# hhv-dcdarknet.net
KiCad netlist of a schematic drawn in EAGLE
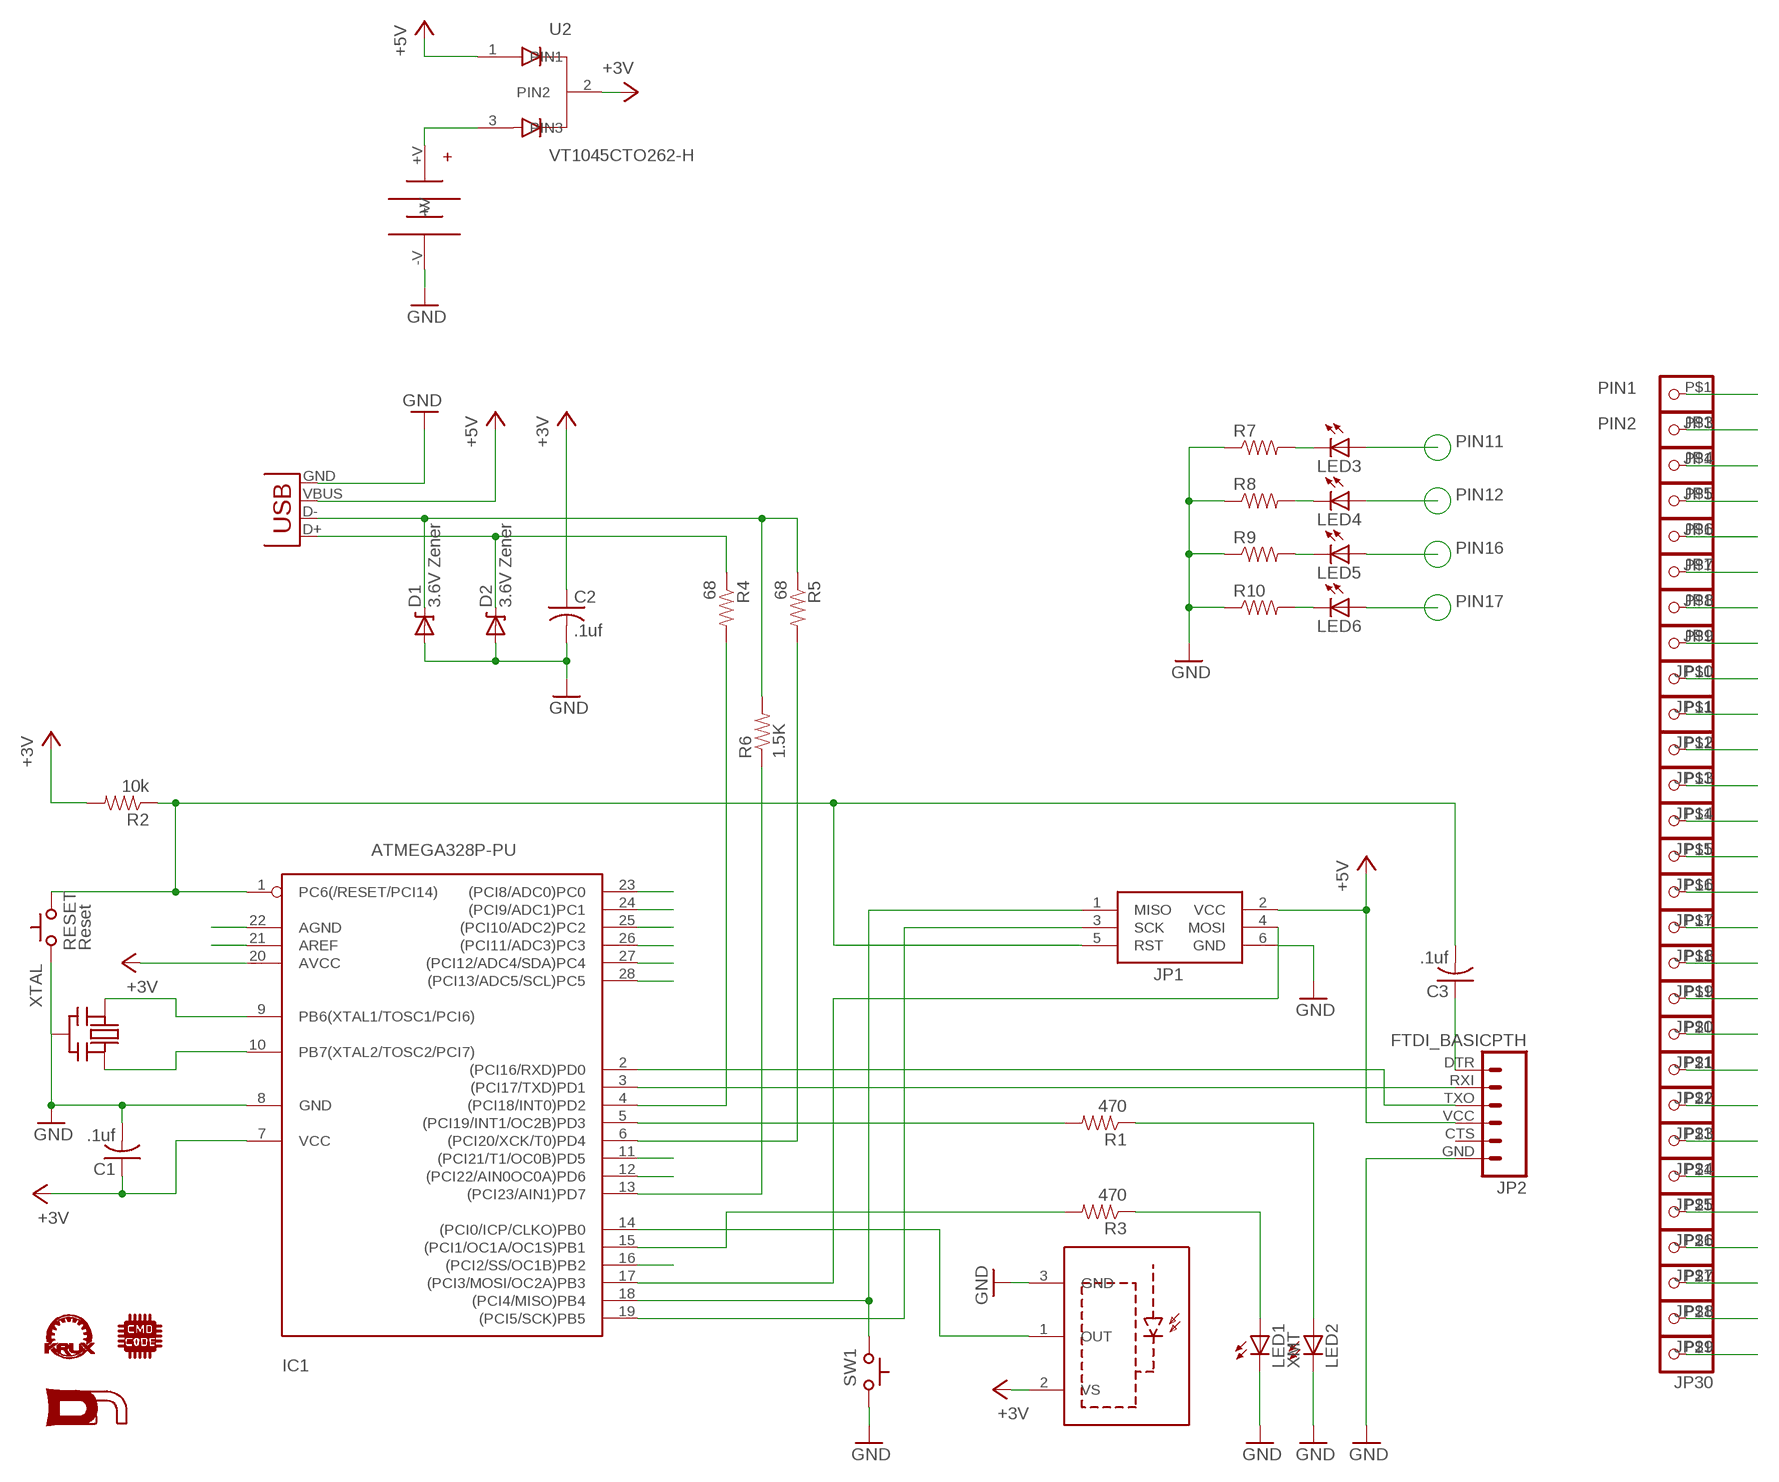
[diagram p0: schematic, sheet 1]

(export (version "E")
  (design (tool "Eeschema 10.0.6"))
  (components
    (comp (ref "C1")
      (value ".1uf")
      (footprint "eagle-import:C025-030X050")
      (libsource (lib "eagle-import") (part "C-US025-030X050"))
    )
    (comp (ref "C2")
      (value ".1uf")
      (footprint "eagle-import:C025-030X050")
      (libsource (lib "eagle-import") (part "C-US025-030X050"))
    )
    (comp (ref "C3")
      (value ".1uf")
      (footprint "eagle-import:C025-030X050")
      (libsource (lib "eagle-import") (part "C-US025-030X050"))
    )
    (comp (ref "D1")
      (value "3.6V Zener")
      (footprint "eagle-import:DIODE-ZENER")
      (libsource (lib "eagle-import") (part "DIODE-ZENERPTH"))
    )
    (comp (ref "D2")
      (value "3.6V Zener")
      (footprint "eagle-import:DIODE-ZENER")
      (libsource (lib "eagle-import") (part "DIODE-ZENERPTH"))
    )
    (comp (ref "IC1")
      (value "ATMEGA328P-PU")
      (footprint "eagle-import:DIL28-3")
      (libsource (lib "eagle-import") (part "ATMEGA168PV-10"))
    )
    (comp (ref "JP1")
      (value "JP1")
      (footprint "eagle-import:AVRISP")
      (libsource (lib "eagle-import") (part "AVRISP-6"))
    )
    (comp (ref "JP2")
      (value "FTDI_BASICPTH")
      (footprint "eagle-import:FTDI_BASIC")
      (libsource (lib "eagle-import") (part "FTDI_BASICPTH"))
    )
    (comp (ref "JP3")
      (value "PINHD-1X11X1_SQUARE")
      (footprint "eagle-import:1X1-SMALL_CUT")
      (libsource (lib "eagle-import") (part "PINHD-1X11X1_SQUARE"))
    )
    (comp (ref "JP4")
      (value "PINHD-1X11X1_SQUARE")
      (footprint "eagle-import:1X1-SMALL_CUT")
      (libsource (lib "eagle-import") (part "PINHD-1X11X1_SQUARE"))
    )
    (comp (ref "JP5")
      (value "PINHD-1X11X1_SQUARE")
      (footprint "eagle-import:1X1-SMALL_CUT")
      (libsource (lib "eagle-import") (part "PINHD-1X11X1_SQUARE"))
    )
    (comp (ref "JP6")
      (value "PINHD-1X11X1_SQUARE")
      (footprint "eagle-import:1X1-SMALL_CUT")
      (libsource (lib "eagle-import") (part "PINHD-1X11X1_SQUARE"))
    )
    (comp (ref "JP7")
      (value "PINHD-1X11X1_SQUARE")
      (footprint "eagle-import:1X1-SMALL_CUT")
      (libsource (lib "eagle-import") (part "PINHD-1X11X1_SQUARE"))
    )
    (comp (ref "JP8")
      (value "PINHD-1X11X1_SQUARE")
      (footprint "eagle-import:1X1-SMALL_CUT")
      (libsource (lib "eagle-import") (part "PINHD-1X11X1_SQUARE"))
    )
    (comp (ref "JP9")
      (value "PINHD-1X11X1_SQUARE")
      (footprint "eagle-import:1X1-SMALL_CUT")
      (libsource (lib "eagle-import") (part "PINHD-1X11X1_SQUARE"))
    )
    (comp (ref "JP10")
      (value "PINHD-1X11X1_SQUARE")
      (footprint "eagle-import:1X1-SMALL_CUT")
      (libsource (lib "eagle-import") (part "PINHD-1X11X1_SQUARE"))
    )
    (comp (ref "JP11")
      (value "PINHD-1X11X1_SQUARE")
      (footprint "eagle-import:1X1-SMALL_CUT")
      (libsource (lib "eagle-import") (part "PINHD-1X11X1_SQUARE"))
    )
    (comp (ref "JP12")
      (value "PINHD-1X11X1_SQUARE")
      (footprint "eagle-import:1X1-SMALL_CUT")
      (libsource (lib "eagle-import") (part "PINHD-1X11X1_SQUARE"))
    )
    (comp (ref "JP13")
      (value "PINHD-1X11X1_SQUARE")
      (footprint "eagle-import:1X1-SMALL_CUT")
      (libsource (lib "eagle-import") (part "PINHD-1X11X1_SQUARE"))
    )
    (comp (ref "JP14")
      (value "PINHD-1X11X1_SQUARE")
      (footprint "eagle-import:1X1-SMALL_CUT")
      (libsource (lib "eagle-import") (part "PINHD-1X11X1_SQUARE"))
    )
    (comp (ref "JP15")
      (value "PINHD-1X11X1_SQUARE")
      (footprint "eagle-import:1X1-SMALL_CUT")
      (libsource (lib "eagle-import") (part "PINHD-1X11X1_SQUARE"))
    )
    (comp (ref "JP16")
      (value "PINHD-1X11X1_SQUARE")
      (footprint "eagle-import:1X1-SMALL_CUT")
      (libsource (lib "eagle-import") (part "PINHD-1X11X1_SQUARE"))
    )
    (comp (ref "JP17")
      (value "PINHD-1X11X1_SQUARE")
      (footprint "eagle-import:1X1-SMALL_CUT")
      (libsource (lib "eagle-import") (part "PINHD-1X11X1_SQUARE"))
    )
    (comp (ref "JP18")
      (value "PINHD-1X11X1_SQUARE")
      (footprint "eagle-import:1X1-SMALL_CUT")
      (libsource (lib "eagle-import") (part "PINHD-1X11X1_SQUARE"))
    )
    (comp (ref "JP19")
      (value "PINHD-1X11X1_SQUARE")
      (footprint "eagle-import:1X1-SMALL_CUT")
      (libsource (lib "eagle-import") (part "PINHD-1X11X1_SQUARE"))
    )
    (comp (ref "JP20")
      (value "PINHD-1X11X1_SQUARE")
      (footprint "eagle-import:1X1-SMALL_CUT")
      (libsource (lib "eagle-import") (part "PINHD-1X11X1_SQUARE"))
    )
    (comp (ref "JP21")
      (value "PINHD-1X11X1_SQUARE")
      (footprint "eagle-import:1X1-SMALL_CUT")
      (libsource (lib "eagle-import") (part "PINHD-1X11X1_SQUARE"))
    )
    (comp (ref "JP22")
      (value "PINHD-1X11X1_SQUARE")
      (footprint "eagle-import:1X1-SMALL_CUT")
      (libsource (lib "eagle-import") (part "PINHD-1X11X1_SQUARE"))
    )
    (comp (ref "JP23")
      (value "PINHD-1X11X1_SQUARE")
      (footprint "eagle-import:1X1-SMALL_CUT")
      (libsource (lib "eagle-import") (part "PINHD-1X11X1_SQUARE"))
    )
    (comp (ref "JP24")
      (value "PINHD-1X11X1-SMALL")
      (footprint "eagle-import:1X1-SMALL")
      (libsource (lib "eagle-import") (part "PINHD-1X11X1-SMALL"))
    )
    (comp (ref "JP25")
      (value "PINHD-1X11X1-SMALL")
      (footprint "eagle-import:1X1-SMALL")
      (libsource (lib "eagle-import") (part "PINHD-1X11X1-SMALL"))
    )
    (comp (ref "JP26")
      (value "PINHD-1X11X1_SQUARE")
      (footprint "eagle-import:1X1-SMALL_CUT")
      (libsource (lib "eagle-import") (part "PINHD-1X11X1_SQUARE"))
    )
    (comp (ref "JP27")
      (value "PINHD-1X11X1-SMALL")
      (footprint "eagle-import:1X1-SMALL")
      (libsource (lib "eagle-import") (part "PINHD-1X11X1-SMALL"))
    )
    (comp (ref "JP28")
      (value "PINHD-1X11X1_SQUARE")
      (footprint "eagle-import:1X1-SMALL_CUT")
      (libsource (lib "eagle-import") (part "PINHD-1X11X1_SQUARE"))
    )
    (comp (ref "JP29")
      (value "PINHD-1X11X1-SMALL")
      (footprint "eagle-import:1X1-SMALL")
      (libsource (lib "eagle-import") (part "PINHD-1X11X1-SMALL"))
    )
    (comp (ref "JP30")
      (value "PINHD-1X11X1-SMALL")
      (footprint "eagle-import:1X1-SMALL")
      (libsource (lib "eagle-import") (part "PINHD-1X11X1-SMALL"))
    )
    (comp (ref "LED1")
      (value "XMT")
      (footprint "eagle-import:LED5MM-FLAT")
      (libsource (lib "eagle-import") (part "LED5MM-FLAT"))
    )
    (comp (ref "LED2")
      (value "LED5MM-FLAT")
      (footprint "eagle-import:LED5MM-FLAT")
      (libsource (lib "eagle-import") (part "LED5MM-FLAT"))
    )
    (comp (ref "LED3")
      (value "LED1206")
      (footprint "eagle-import:LED-1206")
      (libsource (lib "eagle-import") (part "SparkFun_LED1206"))
    )
    (comp (ref "LED4")
      (value "LED1206")
      (footprint "eagle-import:LED-1206")
      (libsource (lib "eagle-import") (part "SparkFun_LED1206"))
    )
    (comp (ref "LED5")
      (value "LED1206")
      (footprint "eagle-import:LED-1206")
      (libsource (lib "eagle-import") (part "SparkFun_LED1206"))
    )
    (comp (ref "LED6")
      (value "LED1206")
      (footprint "eagle-import:LED-1206")
      (libsource (lib "eagle-import") (part "SparkFun_LED1206"))
    )
    (comp (ref "R1")
      (value "470")
      (footprint "eagle-import:AXIAL-0.3")
      (libsource (lib "eagle-import") (part "RESISTORAXIAL-0.3"))
    )
    (comp (ref "R2")
      (value "10k")
      (footprint "eagle-import:AXIAL-0.3")
      (libsource (lib "eagle-import") (part "RESISTORAXIAL-0.3"))
    )
    (comp (ref "R3")
      (value "470")
      (footprint "eagle-import:AXIAL-0.3")
      (libsource (lib "eagle-import") (part "RESISTORAXIAL-0.3"))
    )
    (comp (ref "R4")
      (value "68")
      (footprint "eagle-import:AXIAL-0.3")
      (libsource (lib "eagle-import") (part "RESISTORAXIAL-0.3"))
    )
    (comp (ref "R5")
      (value "68")
      (footprint "eagle-import:AXIAL-0.3")
      (libsource (lib "eagle-import") (part "RESISTORAXIAL-0.3"))
    )
    (comp (ref "R6")
      (value "1.5K")
      (footprint "eagle-import:AXIAL-0.3")
      (libsource (lib "eagle-import") (part "RESISTORAXIAL-0.3"))
    )
    (comp (ref "R7")
      (value "RESISTOR1206")
      (footprint "eagle-import:1206")
      (libsource (lib "eagle-import") (part "SparkFun_RESISTOR1206"))
    )
    (comp (ref "R8")
      (value "RESISTOR1206")
      (footprint "eagle-import:1206")
      (libsource (lib "eagle-import") (part "SparkFun_RESISTOR1206"))
    )
    (comp (ref "R9")
      (value "RESISTOR1206")
      (footprint "eagle-import:1206")
      (libsource (lib "eagle-import") (part "SparkFun_RESISTOR1206"))
    )
    (comp (ref "R10")
      (value "RESISTOR1206")
      (footprint "eagle-import:1206")
      (libsource (lib "eagle-import") (part "SparkFun_RESISTOR1206"))
    )
    (comp (ref "RESET")
      (value "Reset")
      (footprint "eagle-import:TACTILE-2PIN")
      (libsource (lib "eagle-import") (part "SWITCH_TACTILETACTILE-2PIN"))
    )
    (comp (ref "SW1")
      (value "SWITCH_TACTILETACTILE-2PIN")
      (footprint "eagle-import:TACTILE-2PIN")
      (libsource (lib "eagle-import") (part "SWITCH_TACTILETACTILE-2PIN"))
    )
    (comp (ref "U$1")
      (value "DN_LOGO")
      (footprint "eagle-import:DN_LOGO")
      (libsource (lib "eagle-import") (part "DN_LOGO"))
    )
    (comp (ref "U$2")
      (value "CMDC0DE_LOGO")
      (footprint "eagle-import:CMDC0DE")
      (libsource (lib "eagle-import") (part "CMDC0DE_LOGO"))
    )
    (comp (ref "U$3")
      (value "KRUX_LOGO")
      (footprint "eagle-import:KRUX_LOGO")
      (libsource (lib "eagle-import") (part "KRUX_LOGO"))
    )
    (comp (ref "U$5")
      (value "12BH423-GR3-CELL_NOBORDER")
      (footprint "eagle-import:3-AAA-CELL_NOBORDER")
      (libsource (lib "eagle-import") (part "12BH423-GR3-CELL_NOBORDER"))
    )
    (comp (ref "U1")
      (value "RCV")
      (footprint "eagle-import:IR-MODULE")
      (libsource (lib "eagle-import") (part "SOP22"))
    )
    (comp (ref "U2")
      (value "VT1045CTO262-H")
      (footprint "eagle-import:TO262-H")
      (libsource (lib "eagle-import") (part "VT1045CTO262-H"))
    )
    (comp (ref "X2")
      (value "USB")
      (footprint "eagle-import:USB-B-PTH")
      (libsource (lib "eagle-import") (part "USBPTH"))
    )
    (comp (ref "XTAL")
      (value "CERMOSCILL-THM")
      (footprint "eagle-import:CERM_OSC")
      (libsource (lib "eagle-import") (part "CERMOSCILL-THM"))
    )
  )
  (nets
    (net (code "1") (name "+3V") (class "Default")
      (node (ref "C1") (pin "1") (pinfunction "1_1") (pintype "passive"))
      (node (ref "C2") (pin "1") (pinfunction "1_1") (pintype "passive"))
      (node (ref "IC1") (pin "20") (pinfunction "AVCC_20") (pintype "bidirectional"))
      (node (ref "IC1") (pin "7") (pinfunction "VCC_7") (pintype "bidirectional"))
      (node (ref "JP22") (pin "P$1") (pinfunction "1_P$1") (pintype "passive"))
      (node (ref "JP9") (pin "P$1") (pinfunction "1_P$1") (pintype "passive"))
      (node (ref "R2") (pin "P$2") (pinfunction "2_P$2") (pintype "passive"))
      (node (ref "U1") (pin "2") (pinfunction "VS_2") (pintype "bidirectional"))
      (node (ref "U2") (pin "2") (pinfunction "PIN2_2") (pintype "bidirectional"))
    )
    (net (code "2") (name "+5V") (class "Default")
      (node (ref "JP1") (pin "2") (pinfunction "VCC_2") (pintype "power_in"))
      (node (ref "JP2") (pin "VCC") (pinfunction "4_VCC") (pintype "passive"))
      (node (ref "U2") (pin "1") (pinfunction "PIN1_1") (pintype "bidirectional"))
      (node (ref "X2") (pin "VBUS") (pinfunction "VBUS_VBUS") (pintype "bidirectional"))
    )
    (net (code "3") (name "/PIN1") (class "Default")
      (node (ref "C3") (pin "2") (pinfunction "2_2") (pintype "passive"))
      (node (ref "IC1") (pin "1") (pinfunction "PC6(/RESET/PCI14)_1") (pintype "bidirectional"))
      (node (ref "JP1") (pin "5") (pinfunction "RST_5") (pintype "output"))
      (node (ref "JP3") (pin "P$1") (pinfunction "1_P$1") (pintype "passive"))
      (node (ref "R2") (pin "P$1") (pinfunction "1_P$1") (pintype "passive"))
      (node (ref "RESET") (pin "P$1") (pinfunction "A_P$1") (pintype "passive"))
    )
    (net (code "4") (name "/PIN2") (class "Default")
      (node (ref "IC1") (pin "2") (pinfunction "(PCI16/RXD)PD0_2") (pintype "bidirectional"))
      (node (ref "JP2") (pin "TXO") (pinfunction "3_TXO") (pintype "passive"))
      (node (ref "JP4") (pin "P$1") (pinfunction "1_P$1") (pintype "passive"))
    )
    (net (code "5") (name "/PIN3") (class "Default")
      (node (ref "IC1") (pin "3") (pinfunction "(PCI17/TXD)PD1_3") (pintype "bidirectional"))
      (node (ref "JP2") (pin "RXI") (pinfunction "2_RXI") (pintype "passive"))
      (node (ref "JP5") (pin "P$1") (pinfunction "1_P$1") (pintype "passive"))
    )
    (net (code "6") (name "/PIN4") (class "Default")
      (node (ref "IC1") (pin "4") (pinfunction "(PCI18/INT0)PD2_4") (pintype "bidirectional"))
      (node (ref "JP6") (pin "P$1") (pinfunction "1_P$1") (pintype "passive"))
      (node (ref "R4") (pin "P$2") (pinfunction "2_P$2") (pintype "passive"))
    )
    (net (code "7") (name "/PIN5") (class "Default")
      (node (ref "IC1") (pin "5") (pinfunction "(PCI19/INT1/OC2B)PD3_5") (pintype "bidirectional"))
      (node (ref "JP7") (pin "P$1") (pinfunction "1_P$1") (pintype "passive"))
      (node (ref "R1") (pin "P$2") (pinfunction "2_P$2") (pintype "passive"))
    )
    (net (code "8") (name "/PIN6") (class "Default")
      (node (ref "IC1") (pin "6") (pinfunction "(PCI20/XCK/T0)PD4_6") (pintype "bidirectional"))
      (node (ref "JP8") (pin "P$1") (pinfunction "1_P$1") (pintype "passive"))
      (node (ref "R5") (pin "P$2") (pinfunction "2_P$2") (pintype "passive"))
    )
    (net (code "9") (name "/PIN9") (class "Default")
      (node (ref "IC1") (pin "9") (pinfunction "PB6(XTAL1/TOSC1/PCI6)_9") (pintype "bidirectional"))
      (node (ref "JP11") (pin "P$1") (pinfunction "1_P$1") (pintype "passive"))
      (node (ref "XTAL") (pin "P$1") (pinfunction "IN_P$1") (pintype "bidirectional"))
    )
    (net (code "10") (name "/PIN10") (class "Default")
      (node (ref "IC1") (pin "10") (pinfunction "PB7(XTAL2/TOSC2/PCI7)_10") (pintype "bidirectional"))
      (node (ref "JP12") (pin "P$1") (pinfunction "1_P$1") (pintype "passive"))
      (node (ref "XTAL") (pin "P$3") (pinfunction "OUT_P$3") (pintype "bidirectional"))
    )
    (net (code "11") (name "/PIN11") (class "Default")
      (node (ref "IC1") (pin "11") (pinfunction "(PCI21/T1/OC0B)PD5_11") (pintype "bidirectional"))
      (node (ref "JP13") (pin "P$1") (pinfunction "1_P$1") (pintype "passive"))
      (node (ref "LED3") (pin "A") (pinfunction "A_A") (pintype "passive"))
    )
    (net (code "12") (name "/PIN12") (class "Default")
      (node (ref "IC1") (pin "12") (pinfunction "(PCI22/AIN0OC0A)PD6_12") (pintype "bidirectional"))
      (node (ref "JP14") (pin "P$1") (pinfunction "1_P$1") (pintype "passive"))
      (node (ref "LED4") (pin "A") (pinfunction "A_A") (pintype "passive"))
    )
    (net (code "13") (name "/PIN13") (class "Default")
      (node (ref "IC1") (pin "13") (pinfunction "(PCI23/AIN1)PD7_13") (pintype "bidirectional"))
      (node (ref "JP15") (pin "P$1") (pinfunction "1_P$1") (pintype "passive"))
      (node (ref "R6") (pin "P$1") (pinfunction "1_P$1") (pintype "passive"))
    )
    (net (code "14") (name "/PIN14") (class "Default")
      (node (ref "IC1") (pin "14") (pinfunction "(PCI0/ICP/CLKO)PB0_14") (pintype "bidirectional"))
      (node (ref "JP16") (pin "P$1") (pinfunction "1_P$1") (pintype "passive"))
      (node (ref "U1") (pin "1") (pinfunction "OUT_1") (pintype "bidirectional"))
    )
    (net (code "15") (name "/PIN15") (class "Default")
      (node (ref "IC1") (pin "15") (pinfunction "(PCI1/OC1A/OC1S)PB1_15") (pintype "bidirectional"))
      (node (ref "JP17") (pin "P$1") (pinfunction "1_P$1") (pintype "passive"))
      (node (ref "R3") (pin "P$2") (pinfunction "2_P$2") (pintype "passive"))
    )
    (net (code "16") (name "/PIN16") (class "Default")
      (node (ref "IC1") (pin "16") (pinfunction "(PCI2/SS/OC1B)PB2_16") (pintype "bidirectional"))
      (node (ref "JP18") (pin "P$1") (pinfunction "1_P$1") (pintype "passive"))
      (node (ref "LED5") (pin "A") (pinfunction "A_A") (pintype "passive"))
    )
    (net (code "17") (name "/PIN17") (class "Default")
      (node (ref "IC1") (pin "17") (pinfunction "(PCI3/MOSI/OC2A)PB3_17") (pintype "bidirectional"))
      (node (ref "JP1") (pin "4") (pinfunction "MOSI_4") (pintype "output"))
      (node (ref "JP19") (pin "P$1") (pinfunction "1_P$1") (pintype "passive"))
      (node (ref "LED6") (pin "A") (pinfunction "A_A") (pintype "passive"))
    )
    (net (code "18") (name "/PIN18") (class "Default")
      (node (ref "IC1") (pin "18") (pinfunction "(PCI4/MISO)PB4_18") (pintype "bidirectional"))
      (node (ref "JP1") (pin "1") (pinfunction "MISO_1") (pintype "input"))
      (node (ref "JP20") (pin "P$1") (pinfunction "1_P$1") (pintype "passive"))
      (node (ref "SW1") (pin "P$2") (pinfunction "C_P$2") (pintype "passive"))
    )
    (net (code "19") (name "/PIN19") (class "Default")
      (node (ref "IC1") (pin "19") (pinfunction "(PCI5/SCK)PB5_19") (pintype "bidirectional"))
      (node (ref "JP1") (pin "3") (pinfunction "SCK_3") (pintype "output"))
      (node (ref "JP21") (pin "P$1") (pinfunction "1_P$1") (pintype "passive"))
    )
    (net (code "20") (name "/PIN21") (class "Default")
      (node (ref "IC1") (pin "21") (pinfunction "AREF_21") (pintype "bidirectional"))
      (node (ref "JP23") (pin "P$1") (pinfunction "1_P$1") (pintype "passive"))
    )
    (net (code "21") (name "/PIN22") (class "Default")
      (node (ref "IC1") (pin "22") (pinfunction "AGND_22") (pintype "bidirectional"))
      (node (ref "JP24") (pin "P$1") (pinfunction "1_P$1") (pintype "passive"))
    )
    (net (code "22") (name "/PIN23") (class "Default")
      (node (ref "IC1") (pin "23") (pinfunction "(PCI8/ADC0)PC0_23") (pintype "bidirectional"))
      (node (ref "JP25") (pin "P$1") (pinfunction "1_P$1") (pintype "passive"))
    )
    (net (code "23") (name "/PIN24") (class "Default")
      (node (ref "IC1") (pin "24") (pinfunction "(PCI9/ADC1)PC1_24") (pintype "bidirectional"))
      (node (ref "JP26") (pin "P$1") (pinfunction "1_P$1") (pintype "passive"))
    )
    (net (code "24") (name "/PIN25") (class "Default")
      (node (ref "IC1") (pin "25") (pinfunction "(PCI10/ADC2)PC2_25") (pintype "bidirectional"))
      (node (ref "JP27") (pin "P$1") (pinfunction "1_P$1") (pintype "passive"))
    )
    (net (code "25") (name "/PIN26") (class "Default")
      (node (ref "IC1") (pin "26") (pinfunction "(PCI11/ADC3)PC3_26") (pintype "bidirectional"))
      (node (ref "JP28") (pin "P$1") (pinfunction "1_P$1") (pintype "passive"))
    )
    (net (code "26") (name "/PIN27") (class "Default")
      (node (ref "IC1") (pin "27") (pinfunction "(PCI12/ADC4/SDA)PC4_27") (pintype "bidirectional"))
      (node (ref "JP29") (pin "P$1") (pinfunction "1_P$1") (pintype "passive"))
    )
    (net (code "27") (name "/PIN28") (class "Default")
      (node (ref "IC1") (pin "28") (pinfunction "(PCI13/ADC5/SCL)PC5_28") (pintype "bidirectional"))
      (node (ref "JP30") (pin "P$1") (pinfunction "1_P$1") (pintype "passive"))
    )
    (net (code "28") (name "GND") (class "Default")
      (node (ref "C1") (pin "2") (pinfunction "2_2") (pintype "passive"))
      (node (ref "C2") (pin "2") (pinfunction "2_2") (pintype "passive"))
      (node (ref "D1") (pin "P$2") (pinfunction "A_P$2") (pintype "passive"))
      (node (ref "D2") (pin "P$2") (pinfunction "A_P$2") (pintype "passive"))
      (node (ref "IC1") (pin "8") (pinfunction "GND_8") (pintype "bidirectional"))
      (node (ref "JP1") (pin "6") (pinfunction "GND_6") (pintype "power_in"))
      (node (ref "JP10") (pin "P$1") (pinfunction "1_P$1") (pintype "passive"))
      (node (ref "JP2") (pin "GND") (pinfunction "6_GND") (pintype "passive"))
      (node (ref "LED1") (pin "K") (pinfunction "C_K") (pintype "passive"))
      (node (ref "LED2") (pin "K") (pinfunction "C_K") (pintype "passive"))
      (node (ref "R10") (pin "1") (pinfunction "1_1") (pintype "passive"))
      (node (ref "R7") (pin "1") (pinfunction "1_1") (pintype "passive"))
      (node (ref "R8") (pin "1") (pinfunction "1_1") (pintype "passive"))
      (node (ref "R9") (pin "1") (pinfunction "1_1") (pintype "passive"))
      (node (ref "RESET") (pin "P$2") (pinfunction "C_P$2") (pintype "passive"))
      (node (ref "SW1") (pin "P$1") (pinfunction "A_P$1") (pintype "passive"))
      (node (ref "U$5") (pin "-V") (pinfunction "-V_-V") (pintype "bidirectional"))
      (node (ref "U1") (pin "3") (pinfunction "GND_3") (pintype "bidirectional"))
      (node (ref "X2") (pin "GND") (pinfunction "GND_GND") (pintype "bidirectional"))
      (node (ref "XTAL") (pin "P$2") (pinfunction "GND_P$2") (pintype "bidirectional"))
    )
    (net (code "29") (name "Net-(D1-C)") (class "Default")
      (node (ref "D1") (pin "P$1") (pinfunction "C_P$1") (pintype "passive"))
      (node (ref "R5") (pin "P$1") (pinfunction "1_P$1") (pintype "passive"))
      (node (ref "R6") (pin "P$2") (pinfunction "2_P$2") (pintype "passive"))
      (node (ref "X2") (pin "D-") (pinfunction "D-_D-") (pintype "bidirectional"))
    )
    (net (code "30") (name "Net-(D2-C)") (class "Default")
      (node (ref "D2") (pin "P$1") (pinfunction "C_P$1") (pintype "passive"))
      (node (ref "R4") (pin "P$1") (pinfunction "1_P$1") (pintype "passive"))
      (node (ref "X2") (pin "D+") (pinfunction "D+_D+") (pintype "bidirectional"))
    )
    (net (code "31") (name "Net-(JP2-1)") (class "Default")
      (node (ref "C3") (pin "1") (pinfunction "1_1") (pintype "passive"))
      (node (ref "JP2") (pin "DTR") (pinfunction "1_DTR") (pintype "passive"))
    )
    (net (code "32") (name "Net-(LED3-PadC)") (class "Default")
      (node (ref "LED3") (pin "C") (pinfunction "C_C") (pintype "passive"))
      (node (ref "R7") (pin "2") (pinfunction "2_2") (pintype "passive"))
    )
    (net (code "33") (name "Net-(LED4-PadC)") (class "Default")
      (node (ref "LED4") (pin "C") (pinfunction "C_C") (pintype "passive"))
      (node (ref "R8") (pin "2") (pinfunction "2_2") (pintype "passive"))
    )
    (net (code "34") (name "Net-(LED5-PadC)") (class "Default")
      (node (ref "LED5") (pin "C") (pinfunction "C_C") (pintype "passive"))
      (node (ref "R9") (pin "2") (pinfunction "2_2") (pintype "passive"))
    )
    (net (code "35") (name "Net-(LED6-PadC)") (class "Default")
      (node (ref "LED6") (pin "C") (pinfunction "C_C") (pintype "passive"))
      (node (ref "R10") (pin "2") (pinfunction "2_2") (pintype "passive"))
    )
    (net (code "36") (name "Net-(R1-1)") (class "Default")
      (node (ref "LED2") (pin "A") (pinfunction "A_A") (pintype "passive"))
      (node (ref "R1") (pin "P$1") (pinfunction "1_P$1") (pintype "passive"))
    )
    (net (code "37") (name "Net-(R3-1)") (class "Default")
      (node (ref "LED1") (pin "A") (pinfunction "A_A") (pintype "passive"))
      (node (ref "R3") (pin "P$1") (pinfunction "1_P$1") (pintype "passive"))
    )
    (net (code "38") (name "Net-(U2-PIN3)") (class "Default")
      (node (ref "U$5") (pin "+V") (pinfunction "+V_+V") (pintype "bidirectional"))
      (node (ref "U2") (pin "3") (pinfunction "PIN3_3") (pintype "bidirectional"))
    )
    (net (code "39") (name "unconnected-(JP2-5-PadCTS)") (class "Default")
      (node (ref "JP2") (pin "CTS") (pinfunction "5_CTS") (pintype "passive"))
    )
  )
)
